# Rough-Design.net
KiCad netlist of a schematic drawn in Altium Designer
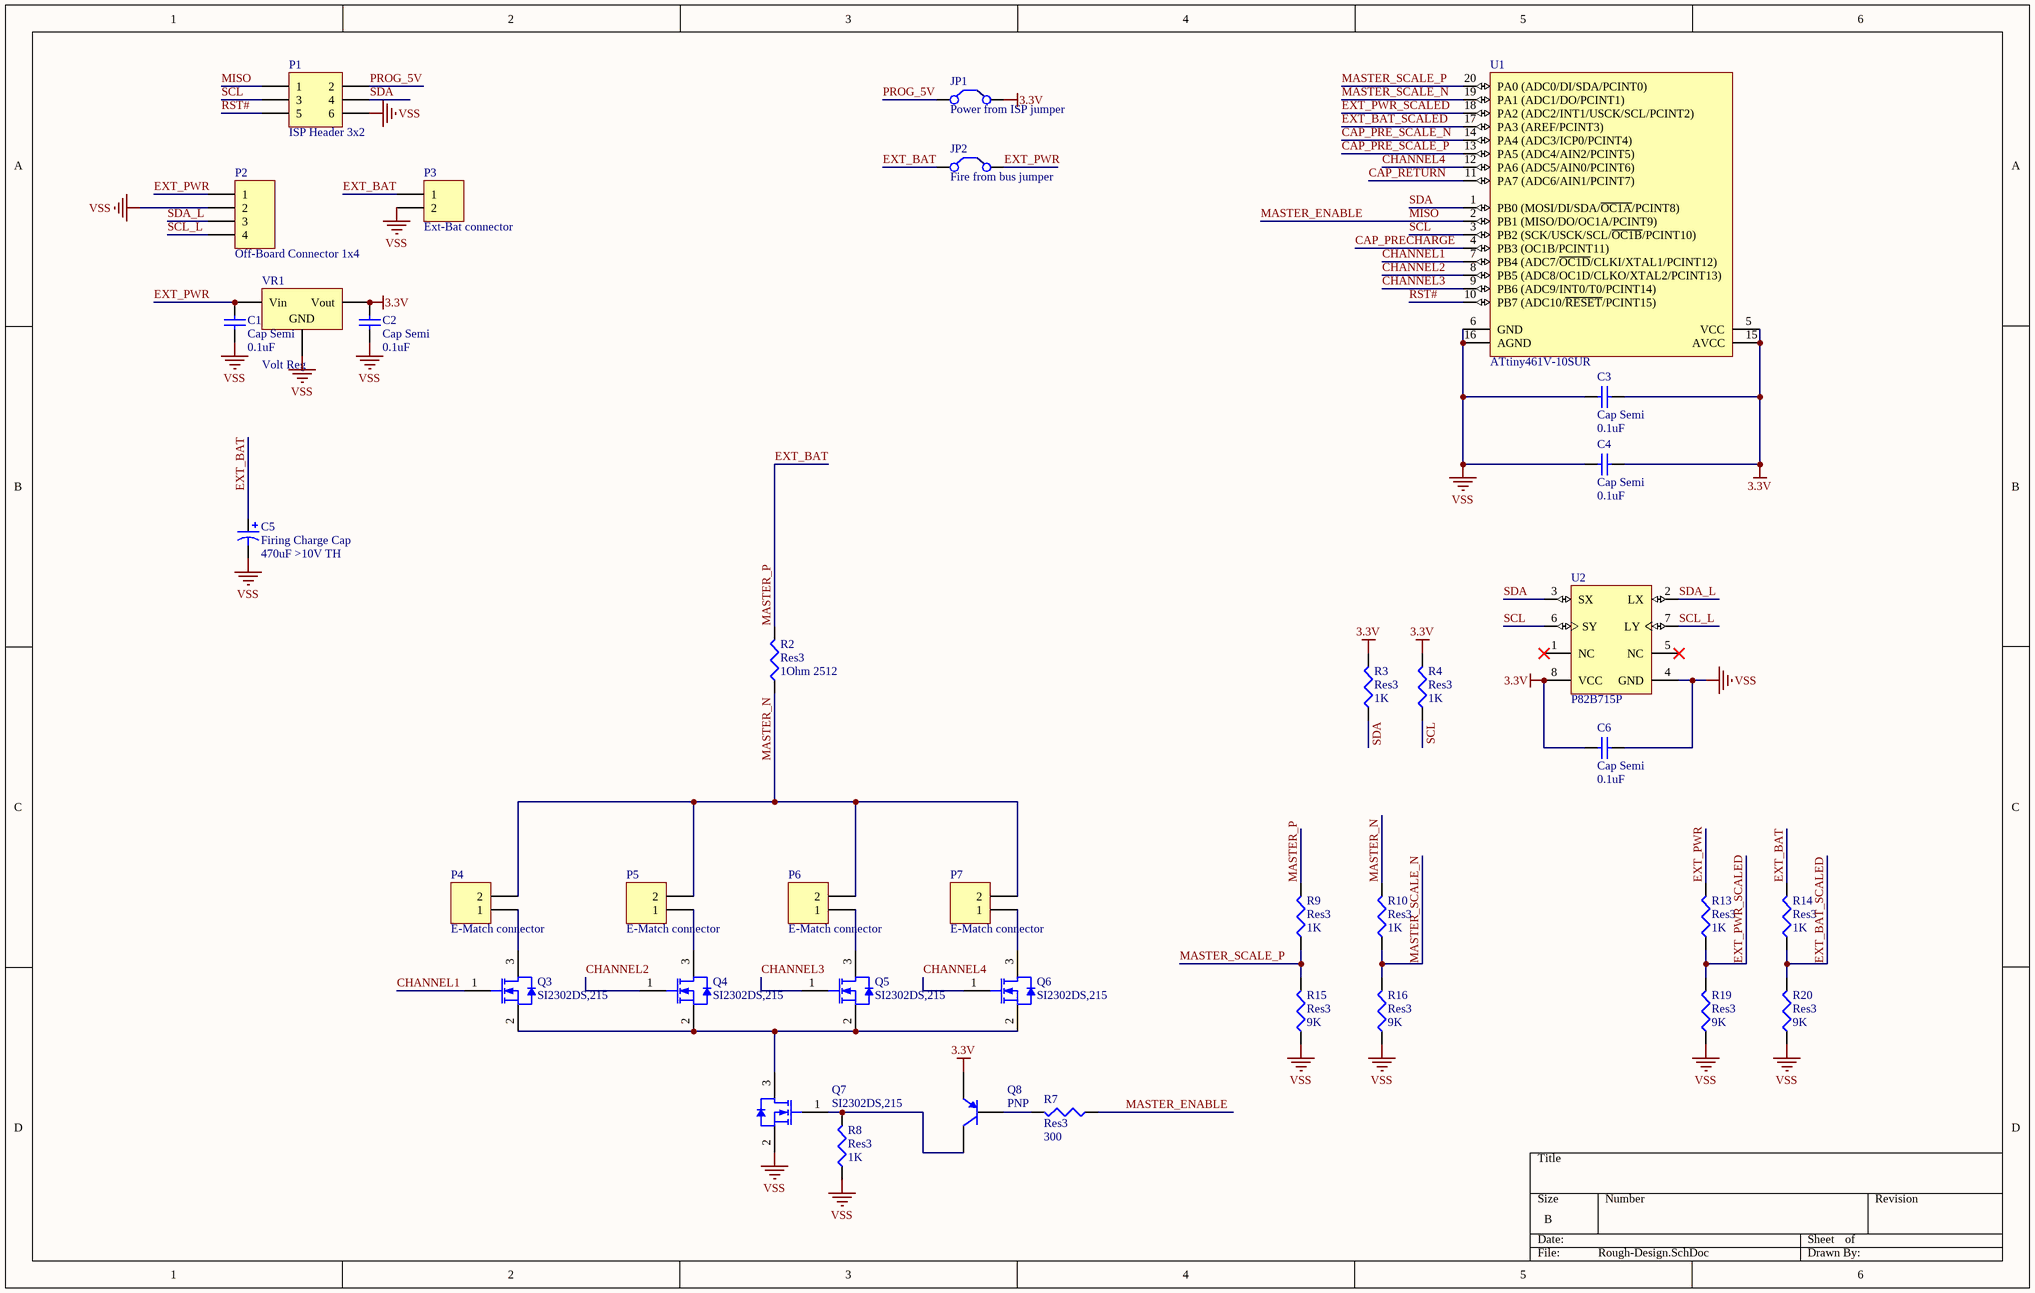
[diagram p0: Rough-Design.SchDoc]

(export (version "E")
  (design (tool "Eeschema 10.0.6"))
  (components
    (comp (ref "C1")
      (value "Cap Semi")
      (footprint "1608[0603]")
      (description "Capacitor (Semiconductor SIM Model)")
      (fields (field (name "ALTIUM_VALUE") "0.1uF") (field (name "PUBLISHER") "Altium Limited"))
      (libsource (lib "Miscellaneous Devices") (part "Cap Semi"))
    )
    (comp (ref "C2")
      (value "Cap Semi")
      (footprint "1608[0603]")
      (description "Capacitor (Semiconductor SIM Model)")
      (fields (field (name "ALTIUM_VALUE") "0.1uF") (field (name "PUBLISHER") "Altium Limited"))
      (libsource (lib "Miscellaneous Devices") (part "Cap Semi"))
    )
    (comp (ref "C3")
      (value "Cap Semi")
      (footprint "C1206")
      (description "Capacitor (Semiconductor SIM Model)")
      (fields (field (name "ALTIUM_VALUE") "0.1uF") (field (name "PUBLISHER") "Altium Limited"))
      (libsource (lib "Miscellaneous Devices") (part "Cap Semi"))
    )
    (comp (ref "C4")
      (value "Cap Semi")
      (footprint "C1206")
      (description "Capacitor (Semiconductor SIM Model)")
      (fields (field (name "ALTIUM_VALUE") "0.1uF") (field (name "PUBLISHER") "Altium Limited"))
      (libsource (lib "Miscellaneous Devices") (part "Cap Semi"))
    )
    (comp (ref "C5")
      (value "Firing Charge Cap")
      (footprint "RB7.6-15")
      (description "Polarized Capacitor (Radial)")
      (fields (field (name "ALTIUM_VALUE") "470uF >10V TH") (field (name "PUBLISHER") "Altium Limited"))
      (libsource (lib "Miscellaneous Devices") (part "Cap Pol1"))
    )
    (comp (ref "C6")
      (value "Cap Semi")
      (footprint "C1206")
      (description "Capacitor (Semiconductor SIM Model)")
      (fields (field (name "ALTIUM_VALUE") "0.1uF") (field (name "PUBLISHER") "Altium Limited"))
      (libsource (lib "Miscellaneous Devices") (part "Cap Semi"))
    )
    (comp (ref "JP1")
      (value "Power from ISP jumper")
      (footprint "SOLDER-JUMPER")
      (description "Solder Configuration Jumper")
      (fields (field (name "PUBLISHER") "Altium Limited"))
      (libsource (lib "SolarCar") (part "SolderJumper"))
    )
    (comp (ref "JP2")
      (value "Fire from bus jumper")
      (footprint "SOLDER-JUMPER")
      (description "Solder Configuration Jumper")
      (fields (field (name "PUBLISHER") "Altium Limited"))
      (libsource (lib "SolarCar") (part "SolderJumper"))
    )
    (comp (ref "P1")
      (value "ISP Header 3x2")
      (footprint "HDR2X3")
      (description "Header, 3-Pin, Dual row")
      (fields (field (name "PUBLISHER") "Altium Limited"))
      (libsource (lib "Miscellaneous Connectors") (part "Header 3X2"))
    )
    (comp (ref "P2")
      (value "Off-Board Connector 1x4")
      (footprint "HDR1X4")
      (description "Header, 4-Pin")
      (fields (field (name "PUBLISHER") "Altium Limited"))
      (libsource (lib "Miscellaneous Connectors") (part "Header 4"))
    )
    (comp (ref "P3")
      (value "Ext-Bat connector")
      (footprint "HDR1X2")
      (description "Header, 2-Pin")
      (fields (field (name "PUBLISHER") "Altium Limited"))
      (libsource (lib "Miscellaneous Connectors") (part "Header 2"))
    )
    (comp (ref "P4")
      (value "E-Match connector")
      (footprint "HDR1X2")
      (description "Header, 2-Pin")
      (fields (field (name "PUBLISHER") "Altium Limited"))
      (libsource (lib "") (part "Header 2_1"))
    )
    (comp (ref "P5")
      (value "E-Match connector")
      (footprint "HDR1X2")
      (description "Header, 2-Pin")
      (fields (field (name "PUBLISHER") "Altium Limited"))
      (libsource (lib "") (part "Header 2_1"))
    )
    (comp (ref "P6")
      (value "E-Match connector")
      (footprint "HDR1X2")
      (description "Header, 2-Pin")
      (fields (field (name "PUBLISHER") "Altium Limited"))
      (libsource (lib "") (part "Header 2_1"))
    )
    (comp (ref "P7")
      (value "E-Match connector")
      (footprint "HDR1X2")
      (description "Header, 2-Pin")
      (fields (field (name "PUBLISHER") "Altium Limited"))
      (libsource (lib "") (part "Header 2_1"))
    )
    (comp (ref "Q3")
      (value "SI2302DS,215")
      (footprint "NXP-SOT23_N")
      (description "N-Channel Enhancement Mode Field-Effect Transistor, 20 V, 2.5 A, 3-Pin SOT23, Tape and Reel")
      (fields (field (name "MANUFACTURER") "NXP Semiconductors"))
      (libsource (lib "Altium Content Vault") (part "NXP-NMOS-GSD-3_B"))
    )
    (comp (ref "Q4")
      (value "SI2302DS,215")
      (footprint "NXP-SOT23_N")
      (description "N-Channel Enhancement Mode Field-Effect Transistor, 20 V, 2.5 A, 3-Pin SOT23, Tape and Reel")
      (fields (field (name "MANUFACTURER") "NXP Semiconductors"))
      (libsource (lib "Altium Content Vault") (part "NXP-NMOS-GSD-3_B"))
    )
    (comp (ref "Q5")
      (value "SI2302DS,215")
      (footprint "NXP-SOT23_N")
      (description "N-Channel Enhancement Mode Field-Effect Transistor, 20 V, 2.5 A, 3-Pin SOT23, Tape and Reel")
      (fields (field (name "MANUFACTURER") "NXP Semiconductors"))
      (libsource (lib "Altium Content Vault") (part "NXP-NMOS-GSD-3_B"))
    )
    (comp (ref "Q6")
      (value "SI2302DS,215")
      (footprint "NXP-SOT23_N")
      (description "N-Channel Enhancement Mode Field-Effect Transistor, 20 V, 2.5 A, 3-Pin SOT23, Tape and Reel")
      (fields (field (name "MANUFACTURER") "NXP Semiconductors"))
      (libsource (lib "Altium Content Vault") (part "NXP-NMOS-GSD-3_B"))
    )
    (comp (ref "Q7")
      (value "SI2302DS,215")
      (footprint "NXP-SOT23_N")
      (description "N-Channel Enhancement Mode Field-Effect Transistor, 20 V, 2.5 A, 3-Pin SOT23, Tape and Reel")
      (fields (field (name "MANUFACTURER") "NXP Semiconductors"))
      (libsource (lib "Altium Content Vault") (part "NXP-NMOS-GSD-3_B"))
    )
    (comp (ref "Q8")
      (value "PNP")
      (footprint "SOT-23B_N")
      (description "PNP Bipolar Transistor")
      (fields (field (name "PUBLISHER") "Altium Limited"))
      (libsource (lib "Miscellaneous Devices") (part "PNP"))
    )
    (comp (ref "R2")
      (value "Res3")
      (footprint "14-1210")
      (description "Resistor")
      (fields (field (name "ALTIUM_VALUE") "1Ohm 2512") (field (name "PUBLISHER") "Altium Limited"))
      (libsource (lib "Miscellaneous Devices") (part "Res3"))
    )
    (comp (ref "R3")
      (value "Res3")
      (footprint "J1-0603")
      (description "Resistor")
      (fields (field (name "ALTIUM_VALUE") "1K") (field (name "PUBLISHER") "Altium Limited"))
      (libsource (lib "Miscellaneous Devices") (part "Res3"))
    )
    (comp (ref "R4")
      (value "Res3")
      (footprint "J1-0603")
      (description "Resistor")
      (fields (field (name "ALTIUM_VALUE") "1K") (field (name "PUBLISHER") "Altium Limited"))
      (libsource (lib "Miscellaneous Devices") (part "Res3"))
    )
    (comp (ref "R7")
      (value "Res3")
      (footprint "J1-0603")
      (description "Resistor")
      (fields (field (name "ALTIUM_VALUE") "300") (field (name "PUBLISHER") "Altium Limited"))
      (libsource (lib "Miscellaneous Devices") (part "Res3"))
    )
    (comp (ref "R8")
      (value "Res3")
      (footprint "J1-0603")
      (description "Resistor")
      (fields (field (name "ALTIUM_VALUE") "1K") (field (name "PUBLISHER") "Altium Limited"))
      (libsource (lib "Miscellaneous Devices") (part "Res3"))
    )
    (comp (ref "R9")
      (value "Res3")
      (footprint "J1-0603")
      (description "Resistor")
      (fields (field (name "ALTIUM_VALUE") "1K") (field (name "PUBLISHER") "Altium Limited"))
      (libsource (lib "Miscellaneous Devices") (part "Res3"))
    )
    (comp (ref "R10")
      (value "Res3")
      (footprint "J1-0603")
      (description "Resistor")
      (fields (field (name "ALTIUM_VALUE") "1K") (field (name "PUBLISHER") "Altium Limited"))
      (libsource (lib "Miscellaneous Devices") (part "Res3"))
    )
    (comp (ref "R13")
      (value "Res3")
      (footprint "J1-0603")
      (description "Resistor")
      (fields (field (name "ALTIUM_VALUE") "1K") (field (name "PUBLISHER") "Altium Limited"))
      (libsource (lib "Miscellaneous Devices") (part "Res3"))
    )
    (comp (ref "R14")
      (value "Res3")
      (footprint "J1-0603")
      (description "Resistor")
      (fields (field (name "ALTIUM_VALUE") "1K") (field (name "PUBLISHER") "Altium Limited"))
      (libsource (lib "Miscellaneous Devices") (part "Res3"))
    )
    (comp (ref "R15")
      (value "Res3")
      (footprint "J1-0603")
      (description "Resistor")
      (fields (field (name "ALTIUM_VALUE") "9K") (field (name "PUBLISHER") "Altium Limited"))
      (libsource (lib "Miscellaneous Devices") (part "Res3"))
    )
    (comp (ref "R16")
      (value "Res3")
      (footprint "J1-0603")
      (description "Resistor")
      (fields (field (name "ALTIUM_VALUE") "9K") (field (name "PUBLISHER") "Altium Limited"))
      (libsource (lib "Miscellaneous Devices") (part "Res3"))
    )
    (comp (ref "R19")
      (value "Res3")
      (footprint "J1-0603")
      (description "Resistor")
      (fields (field (name "ALTIUM_VALUE") "9K") (field (name "PUBLISHER") "Altium Limited"))
      (libsource (lib "Miscellaneous Devices") (part "Res3"))
    )
    (comp (ref "R20")
      (value "Res3")
      (footprint "J1-0603")
      (description "Resistor")
      (fields (field (name "ALTIUM_VALUE") "9K") (field (name "PUBLISHER") "Altium Limited"))
      (libsource (lib "Miscellaneous Devices") (part "Res3"))
    )
    (comp (ref "U1")
      (value "ATtiny461V-10SUR")
      (footprint "20S2_M")
      (libsource (lib "Altium Content Vault") (part "MC-8B-ATT261A-IL20"))
    )
    (comp (ref "U2")
      (value "P82B715P")
      (footprint "P8")
      (description "I2C Bus Extender, 2 Channel Width, 3.0 to 12.0 V, -40 to 85 degC, 8-pin PDIP (P), Pb-Free (RoHS)")
      (fields (field (name "MANUFACTURER") "Texas Instruments"))
      (libsource (lib "Altium Content Vault") (part "TI-P82B715-PDIP_P-8"))
    )
    (comp (ref "VR1")
      (value "Volt Reg")
      (footprint "D2PAK_N")
      (description "Voltage Regulator")
      (fields (field (name "PUBLISHER") "Altium Limited"))
      (libsource (lib "Miscellaneous Devices") (part "Volt Reg"))
    )
  )
  (nets
    (net (code "1") (name "/CAP_PRECHARGE") (class "Default")
      (node (ref "U1") (pin "4") (pinfunction "PB3_(OC1B/PCINT11)_4") (pintype "bidirectional"))
    )
    (net (code "2") (name "/CAP_PRE_SCALE_N") (class "Default")
      (node (ref "U1") (pin "14") (pinfunction "PA4_(ADC3/ICP0/PCINT4)_14") (pintype "bidirectional"))
    )
    (net (code "3") (name "/CAP_PRE_SCALE_P") (class "Default")
      (node (ref "U1") (pin "13") (pinfunction "PA5_(ADC4/AIN2/PCINT5)_13") (pintype "bidirectional"))
    )
    (net (code "4") (name "/CAP_RETURN") (class "Default")
      (node (ref "U1") (pin "11") (pinfunction "PA7_(ADC6/AIN1/PCINT7)_11") (pintype "bidirectional"))
    )
    (net (code "5") (name "/CHANNEL1") (class "Default")
      (node (ref "Q3") (pin "1") (pinfunction "G_1") (pintype "passive"))
      (node (ref "U1") (pin "7") (pinfunction "PB4_(ADC7/~{OC1D}/CLKI/XTAL1/PCINT12)_7") (pintype "bidirectional"))
    )
    (net (code "6") (name "/CHANNEL2") (class "Default")
      (node (ref "Q4") (pin "1") (pinfunction "G_1") (pintype "passive"))
      (node (ref "U1") (pin "8") (pinfunction "PB5_(ADC8/OC1D/CLKO/XTAL2/PCINT13)_8") (pintype "bidirectional"))
    )
    (net (code "7") (name "/CHANNEL3") (class "Default")
      (node (ref "Q5") (pin "1") (pinfunction "G_1") (pintype "passive"))
      (node (ref "U1") (pin "9") (pinfunction "PB6_(ADC9/INT0/T0/PCINT14)_9") (pintype "bidirectional"))
    )
    (net (code "8") (name "/CHANNEL4") (class "Default")
      (node (ref "Q6") (pin "1") (pinfunction "G_1") (pintype "passive"))
      (node (ref "U1") (pin "12") (pinfunction "PA6_(ADC5/AIN0/PCINT6)_12") (pintype "bidirectional"))
    )
    (net (code "9") (name "/EXT_BAT") (class "Default")
      (node (ref "C5") (pin "1") (pinfunction "1_1") (pintype "passive"))
      (node (ref "JP2") (pin "1") (pinfunction "C1_1") (pintype "passive"))
      (node (ref "P3") (pin "1") (pinfunction "1_1") (pintype "passive"))
      (node (ref "R14") (pin "2") (pinfunction "2_2") (pintype "passive"))
      (node (ref "R2") (pin "2") (pinfunction "2_2") (pintype "passive"))
      (node (ref "R9") (pin "2") (pinfunction "2_2") (pintype "passive"))
    )
    (net (code "10") (name "/EXT_BAT_SCALED") (class "Default")
      (node (ref "R14") (pin "1") (pinfunction "1_1") (pintype "passive"))
      (node (ref "R20") (pin "2") (pinfunction "2_2") (pintype "passive"))
      (node (ref "U1") (pin "17") (pinfunction "PA3_(AREF/PCINT3)_17") (pintype "bidirectional"))
    )
    (net (code "11") (name "/EXT_PWR") (class "Default")
      (node (ref "C1") (pin "2") (pinfunction "2_2") (pintype "passive"))
      (node (ref "JP2") (pin "2") (pinfunction "C2_2") (pintype "passive"))
      (node (ref "P2") (pin "1") (pinfunction "1_1") (pintype "passive"))
      (node (ref "R13") (pin "2") (pinfunction "2_2") (pintype "passive"))
      (node (ref "VR1") (pin "1") (pinfunction "Vin_1") (pintype "passive"))
    )
    (net (code "12") (name "/EXT_PWR_SCALED") (class "Default")
      (node (ref "R13") (pin "1") (pinfunction "1_1") (pintype "passive"))
      (node (ref "R19") (pin "2") (pinfunction "2_2") (pintype "passive"))
      (node (ref "U1") (pin "18") (pinfunction "PA2_(ADC2/INT1/USCK/SCL/PCINT2)_18") (pintype "bidirectional"))
    )
    (net (code "13") (name "/MASTER_ENABLE") (class "Default")
      (node (ref "P1") (pin "1") (pinfunction "1_1") (pintype "passive"))
      (node (ref "R7") (pin "1") (pinfunction "1_1") (pintype "passive"))
      (node (ref "U1") (pin "2") (pinfunction "PB1_(MISO/DO/OC1A/PCINT9)_2") (pintype "bidirectional"))
    )
    (net (code "14") (name "/MASTER_N") (class "Default")
      (node (ref "P4") (pin "2") (pinfunction "2_2") (pintype "passive"))
      (node (ref "P5") (pin "2") (pinfunction "2_2") (pintype "passive"))
      (node (ref "P6") (pin "2") (pinfunction "2_2") (pintype "passive"))
      (node (ref "P7") (pin "2") (pinfunction "2_2") (pintype "passive"))
      (node (ref "R10") (pin "2") (pinfunction "2_2") (pintype "passive"))
      (node (ref "R2") (pin "1") (pinfunction "1_1") (pintype "passive"))
    )
    (net (code "15") (name "/MASTER_SCALE_N") (class "Default")
      (node (ref "R10") (pin "1") (pinfunction "1_1") (pintype "passive"))
      (node (ref "R16") (pin "2") (pinfunction "2_2") (pintype "passive"))
      (node (ref "U1") (pin "19") (pinfunction "PA1_(ADC1/DO/PCINT1)_19") (pintype "bidirectional"))
    )
    (net (code "16") (name "/MASTER_SCALE_P") (class "Default")
      (node (ref "R15") (pin "2") (pinfunction "2_2") (pintype "passive"))
      (node (ref "R9") (pin "1") (pinfunction "1_1") (pintype "passive"))
      (node (ref "U1") (pin "20") (pinfunction "PA0_(ADC0/DI/SDA/PCINT0)_20") (pintype "bidirectional"))
    )
    (net (code "17") (name "/PROG_5V") (class "Default")
      (node (ref "JP1") (pin "1") (pinfunction "C1_1") (pintype "passive"))
      (node (ref "P1") (pin "2") (pinfunction "2_2") (pintype "passive"))
    )
    (net (code "18") (name "/RST#") (class "Default")
      (node (ref "P1") (pin "5") (pinfunction "5_5") (pintype "passive"))
      (node (ref "U1") (pin "10") (pinfunction "PB7_(ADC10/~{RESET}/PCINT15)_10") (pintype "bidirectional"))
    )
    (net (code "19") (name "/SCL") (class "Default")
      (node (ref "P1") (pin "3") (pinfunction "3_3") (pintype "passive"))
      (node (ref "R4") (pin "1") (pinfunction "1_1") (pintype "passive"))
      (node (ref "U1") (pin "3") (pinfunction "PB2_(SCK/USCK/SCL/~{OC1B}/PCINT10)_3") (pintype "bidirectional"))
      (node (ref "U2") (pin "6") (pinfunction "SY_6") (pintype "bidirectional"))
    )
    (net (code "20") (name "/SCL_L") (class "Default")
      (node (ref "P2") (pin "4") (pinfunction "4_4") (pintype "passive"))
      (node (ref "U2") (pin "7") (pinfunction "LY_7") (pintype "bidirectional"))
    )
    (net (code "21") (name "/SDA") (class "Default")
      (node (ref "P1") (pin "4") (pinfunction "4_4") (pintype "passive"))
      (node (ref "R3") (pin "1") (pinfunction "1_1") (pintype "passive"))
      (node (ref "U1") (pin "1") (pinfunction "PB0_(MOSI/DI/SDA/~{OC1A}/PCINT8)_1") (pintype "bidirectional"))
      (node (ref "U2") (pin "3") (pinfunction "SX_3") (pintype "bidirectional"))
    )
    (net (code "22") (name "/SDA_L") (class "Default")
      (node (ref "P2") (pin "3") (pinfunction "3_3") (pintype "passive"))
      (node (ref "U2") (pin "2") (pinfunction "LX_2") (pintype "bidirectional"))
    )
    (net (code "23") (name "3.3V") (class "Default")
      (node (ref "C2") (pin "2") (pinfunction "2_2") (pintype "passive"))
      (node (ref "C3") (pin "2") (pinfunction "2_2") (pintype "passive"))
      (node (ref "C4") (pin "2") (pinfunction "2_2") (pintype "passive"))
      (node (ref "C6") (pin "1") (pinfunction "1_1") (pintype "passive"))
      (node (ref "JP1") (pin "2") (pinfunction "C2_2") (pintype "passive"))
      (node (ref "Q8") (pin "3") (pinfunction "E_3") (pintype "passive"))
      (node (ref "R3") (pin "2") (pinfunction "2_2") (pintype "passive"))
      (node (ref "R4") (pin "2") (pinfunction "2_2") (pintype "passive"))
      (node (ref "U1") (pin "15") (pinfunction "AVCC_15") (pintype "power_in"))
      (node (ref "U1") (pin "5") (pinfunction "VCC_5") (pintype "power_in"))
      (node (ref "U2") (pin "8") (pinfunction "VCC_8") (pintype "power_in"))
      (node (ref "VR1") (pin "3") (pinfunction "Vout_3") (pintype "passive"))
    )
    (net (code "24") (name "Net-(Q3-D)") (class "Default")
      (node (ref "P4") (pin "1") (pinfunction "1_1") (pintype "passive"))
      (node (ref "Q3") (pin "3") (pinfunction "D_3") (pintype "passive"))
    )
    (net (code "25") (name "Net-(Q3-S)") (class "Default")
      (node (ref "Q3") (pin "2") (pinfunction "S_2") (pintype "passive"))
      (node (ref "Q4") (pin "2") (pinfunction "S_2") (pintype "passive"))
      (node (ref "Q5") (pin "2") (pinfunction "S_2") (pintype "passive"))
      (node (ref "Q6") (pin "2") (pinfunction "S_2") (pintype "passive"))
      (node (ref "Q7") (pin "3") (pinfunction "D_3") (pintype "passive"))
    )
    (net (code "26") (name "Net-(Q4-D)") (class "Default")
      (node (ref "P5") (pin "1") (pinfunction "1_1") (pintype "passive"))
      (node (ref "Q4") (pin "3") (pinfunction "D_3") (pintype "passive"))
    )
    (net (code "27") (name "Net-(Q5-D)") (class "Default")
      (node (ref "P6") (pin "1") (pinfunction "1_1") (pintype "passive"))
      (node (ref "Q5") (pin "3") (pinfunction "D_3") (pintype "passive"))
    )
    (net (code "28") (name "Net-(Q6-D)") (class "Default")
      (node (ref "P7") (pin "1") (pinfunction "1_1") (pintype "passive"))
      (node (ref "Q6") (pin "3") (pinfunction "D_3") (pintype "passive"))
    )
    (net (code "29") (name "Net-(Q7-G)") (class "Default")
      (node (ref "Q7") (pin "1") (pinfunction "G_1") (pintype "passive"))
      (node (ref "Q8") (pin "1") (pinfunction "C_1") (pintype "passive"))
      (node (ref "R8") (pin "2") (pinfunction "2_2") (pintype "passive"))
    )
    (net (code "30") (name "Net-(Q8-B)") (class "Default")
      (node (ref "Q8") (pin "2") (pinfunction "B_2") (pintype "passive"))
      (node (ref "R7") (pin "2") (pinfunction "2_2") (pintype "passive"))
    )
    (net (code "31") (name "VSS") (class "Default")
      (node (ref "C1") (pin "1") (pinfunction "1_1") (pintype "passive"))
      (node (ref "C2") (pin "1") (pinfunction "1_1") (pintype "passive"))
      (node (ref "C3") (pin "1") (pinfunction "1_1") (pintype "passive"))
      (node (ref "C4") (pin "1") (pinfunction "1_1") (pintype "passive"))
      (node (ref "C5") (pin "2") (pinfunction "2_2") (pintype "passive"))
      (node (ref "C6") (pin "2") (pinfunction "2_2") (pintype "passive"))
      (node (ref "P1") (pin "6") (pinfunction "6_6") (pintype "passive"))
      (node (ref "P2") (pin "2") (pinfunction "2_2") (pintype "passive"))
      (node (ref "P3") (pin "2") (pinfunction "2_2") (pintype "passive"))
      (node (ref "Q7") (pin "2") (pinfunction "S_2") (pintype "passive"))
      (node (ref "R15") (pin "1") (pinfunction "1_1") (pintype "passive"))
      (node (ref "R16") (pin "1") (pinfunction "1_1") (pintype "passive"))
      (node (ref "R19") (pin "1") (pinfunction "1_1") (pintype "passive"))
      (node (ref "R20") (pin "1") (pinfunction "1_1") (pintype "passive"))
      (node (ref "R8") (pin "1") (pinfunction "1_1") (pintype "passive"))
      (node (ref "U1") (pin "16") (pinfunction "AGND_16") (pintype "power_in"))
      (node (ref "U1") (pin "6") (pinfunction "GND_6") (pintype "power_in"))
      (node (ref "U2") (pin "4") (pinfunction "GND_4") (pintype "power_in"))
      (node (ref "VR1") (pin "2") (pinfunction "GND_2") (pintype "passive"))
    )
    (net (code "32") (name "unconnected-(U2-NC-Pad1)") (class "Default")
      (node (ref "U2") (pin "1") (pinfunction "NC_1") (pintype "passive+no_connect"))
    )
    (net (code "33") (name "unconnected-(U2-NC-Pad5)") (class "Default")
      (node (ref "U2") (pin "5") (pinfunction "NC_5") (pintype "passive+no_connect"))
    )
  )
)
